# NIRGM_V3.net
KiCad netlist of a schematic drawn in EAGLE
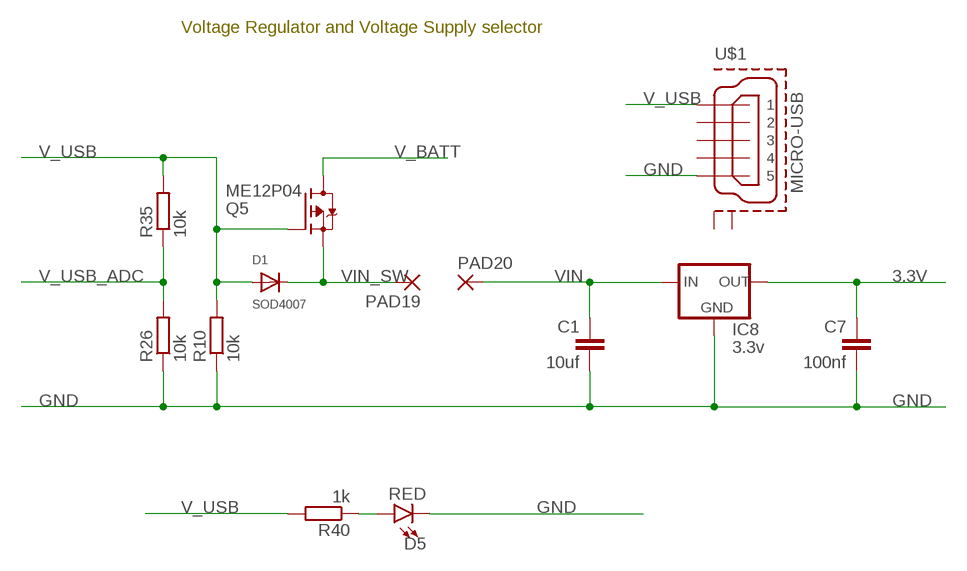
[diagram p0: schematic, sheet 1]
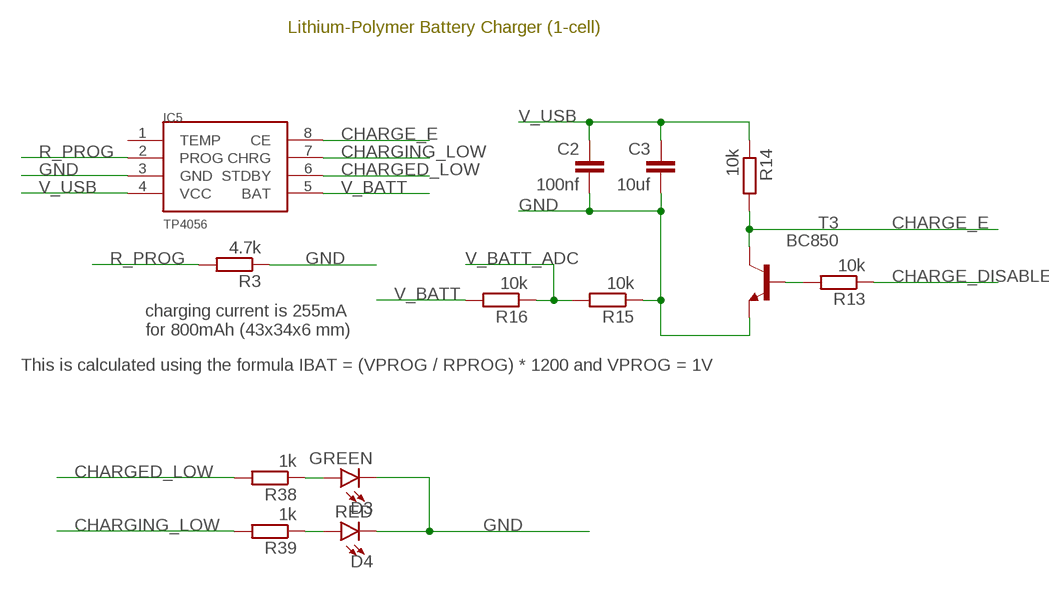
[diagram p1: schematic, sheet 2]
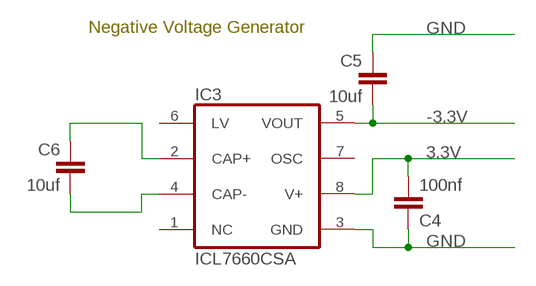
[diagram p2: schematic, sheet 3]
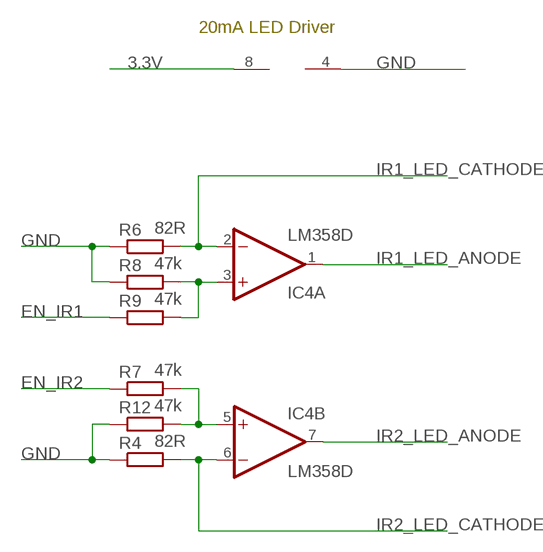
[diagram p3: schematic, sheet 4]
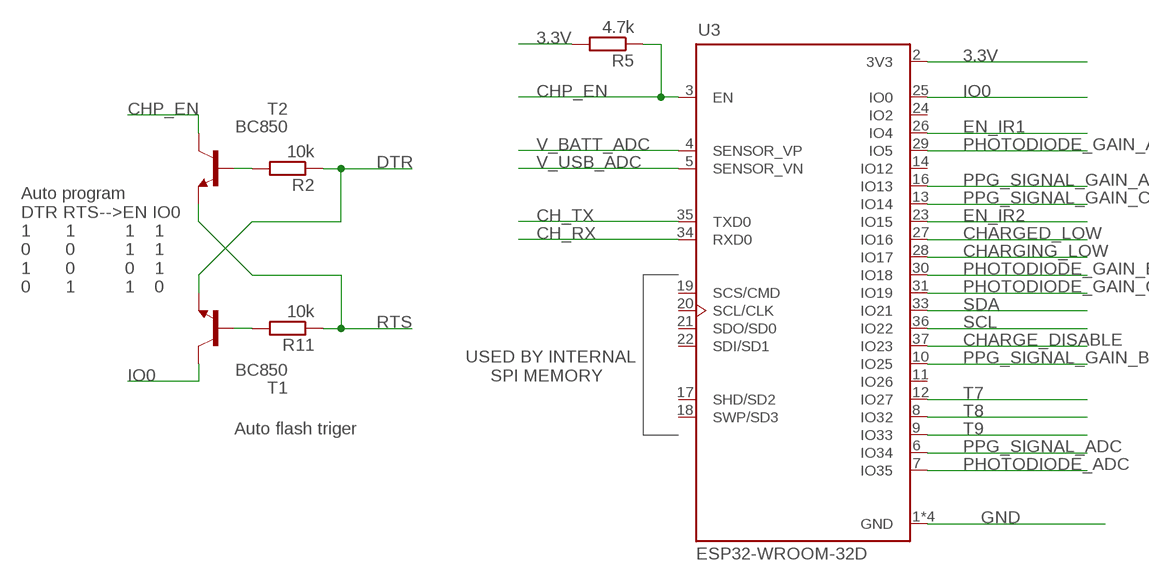
[diagram p4: schematic, sheet 5]
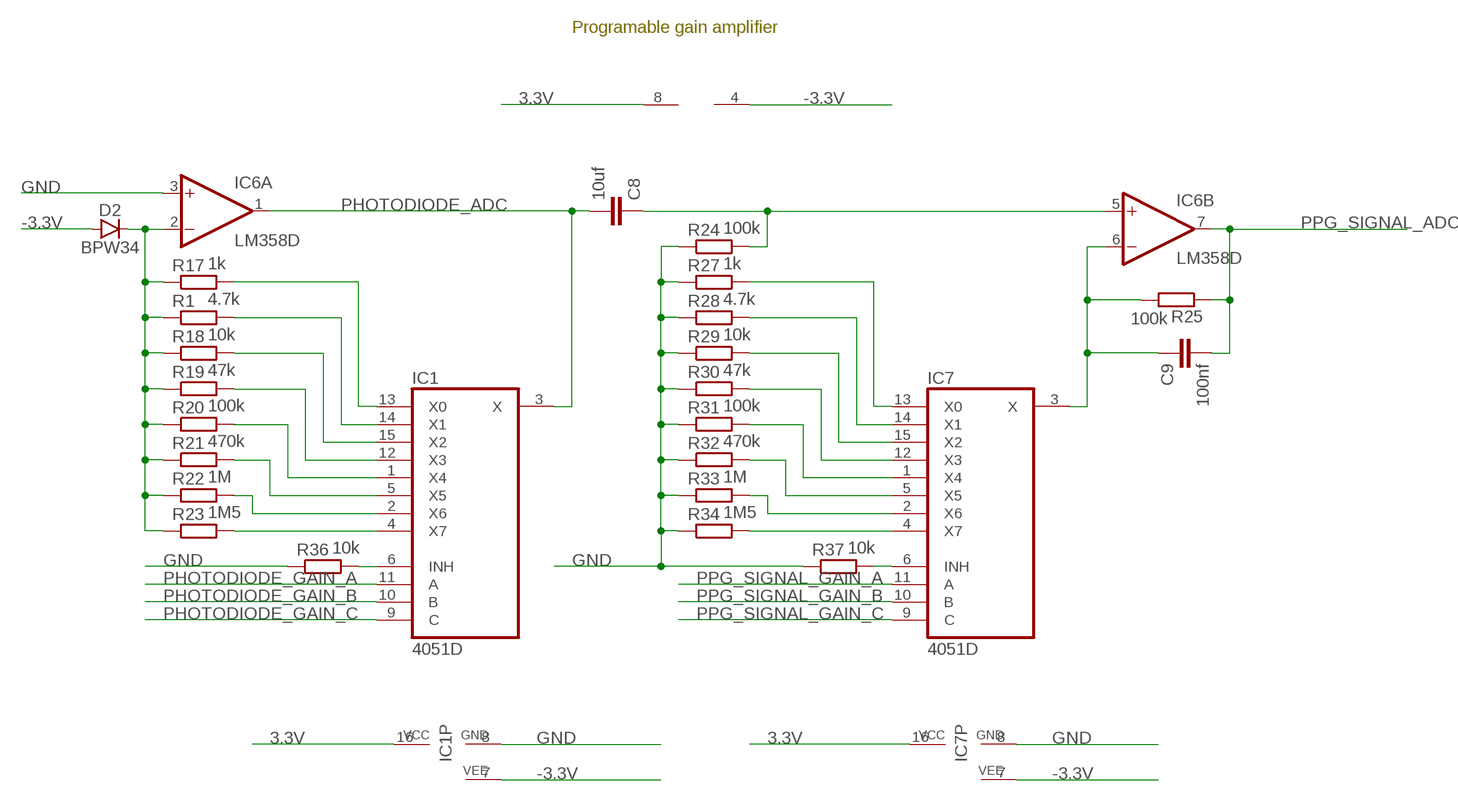
[diagram p5: schematic, sheet 6]
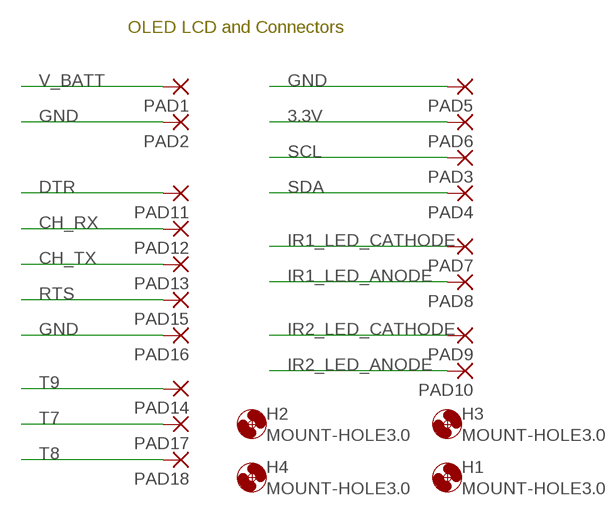
[diagram p6: schematic, sheet 7]

(export (version "E")
  (design (tool "Eeschema 10.0.6"))
  (components
    (comp (ref "C4")
      (value "100nf")
      (footprint "eagle-import:C1206K")
      (libsource (lib "eagle-import") (part "C-EUC1206K"))
    )
    (comp (ref "C5")
      (value "10uf")
      (footprint "eagle-import:C1206K")
      (libsource (lib "eagle-import") (part "C-EUC1206K"))
    )
    (comp (ref "C6")
      (value "10uf")
      (footprint "eagle-import:C1206K")
      (libsource (lib "eagle-import") (part "C-EUC1206K"))
    )
    (comp (ref "IC3")
      (value "ICL7660CSA")
      (footprint "eagle-import:SO08")
      (fields (field (name "MF") "MAXIM"))
      (libsource (lib "eagle-import") (part "ICL7660CSA"))
    )
    (comp (ref "H1")
      (value "MOUNT-HOLE3.0")
      (footprint "eagle-import:3,0")
      (libsource (lib "eagle-import") (part "MOUNT-HOLE3.0"))
    )
    (comp (ref "H2")
      (value "MOUNT-HOLE3.0")
      (footprint "eagle-import:3,0")
      (libsource (lib "eagle-import") (part "MOUNT-HOLE3.0"))
    )
    (comp (ref "H3")
      (value "MOUNT-HOLE3.0")
      (footprint "eagle-import:3,0")
      (libsource (lib "eagle-import") (part "MOUNT-HOLE3.0"))
    )
    (comp (ref "H4")
      (value "MOUNT-HOLE3.0")
      (footprint "eagle-import:3,0")
      (libsource (lib "eagle-import") (part "MOUNT-HOLE3.0"))
    )
    (comp (ref "PAD1")
      (value "WIREPADSMD5-2,5")
      (footprint "eagle-import:5-2,5")
      (libsource (lib "eagle-import") (part "WIREPADSMD5-2,5"))
    )
    (comp (ref "PAD2")
      (value "WIREPADSMD5-2,5")
      (footprint "eagle-import:5-2,5")
      (libsource (lib "eagle-import") (part "WIREPADSMD5-2,5"))
    )
    (comp (ref "PAD3")
      (value "SMD2")
      (footprint "eagle-import:SMD1,27-2,54")
      (libsource (lib "eagle-import") (part "SMD2"))
    )
    (comp (ref "PAD4")
      (value "SMD2")
      (footprint "eagle-import:SMD1,27-2,54")
      (libsource (lib "eagle-import") (part "SMD2"))
    )
    (comp (ref "PAD5")
      (value "SMD2")
      (footprint "eagle-import:SMD1,27-2,54")
      (libsource (lib "eagle-import") (part "SMD2"))
    )
    (comp (ref "PAD6")
      (value "SMD2")
      (footprint "eagle-import:SMD1,27-2,54")
      (libsource (lib "eagle-import") (part "SMD2"))
    )
    (comp (ref "PAD7")
      (value "SMD2")
      (footprint "eagle-import:SMD1,27-2,54")
      (libsource (lib "eagle-import") (part "SMD2"))
    )
    (comp (ref "PAD8")
      (value "SMD2")
      (footprint "eagle-import:SMD1,27-2,54")
      (libsource (lib "eagle-import") (part "SMD2"))
    )
    (comp (ref "PAD9")
      (value "SMD2")
      (footprint "eagle-import:SMD1,27-2,54")
      (libsource (lib "eagle-import") (part "SMD2"))
    )
    (comp (ref "PAD10")
      (value "SMD2")
      (footprint "eagle-import:SMD1,27-2,54")
      (libsource (lib "eagle-import") (part "SMD2"))
    )
    (comp (ref "PAD11")
      (value "SMD2")
      (footprint "eagle-import:SMD1,27-2,54")
      (libsource (lib "eagle-import") (part "SMD2"))
    )
    (comp (ref "PAD12")
      (value "SMD2")
      (footprint "eagle-import:SMD1,27-2,54")
      (libsource (lib "eagle-import") (part "SMD2"))
    )
    (comp (ref "PAD13")
      (value "SMD2")
      (footprint "eagle-import:SMD1,27-2,54")
      (libsource (lib "eagle-import") (part "SMD2"))
    )
    (comp (ref "PAD14")
      (value "SMD2")
      (footprint "eagle-import:SMD1,27-2,54")
      (libsource (lib "eagle-import") (part "SMD2"))
    )
    (comp (ref "PAD15")
      (value "SMD2")
      (footprint "eagle-import:SMD1,27-2,54")
      (libsource (lib "eagle-import") (part "SMD2"))
    )
    (comp (ref "PAD16")
      (value "SMD2")
      (footprint "eagle-import:SMD1,27-2,54")
      (libsource (lib "eagle-import") (part "SMD2"))
    )
    (comp (ref "PAD17")
      (value "SMD2")
      (footprint "eagle-import:SMD1,27-2,54")
      (libsource (lib "eagle-import") (part "SMD2"))
    )
    (comp (ref "PAD18")
      (value "SMD2")
      (footprint "eagle-import:SMD1,27-2,54")
      (libsource (lib "eagle-import") (part "SMD2"))
    )
    (comp (ref "C8")
      (value "10uf")
      (footprint "eagle-import:C1206K")
      (libsource (lib "eagle-import") (part "C-EUC1206K"))
    )
    (comp (ref "C9")
      (value "100nf")
      (footprint "eagle-import:C1206K")
      (libsource (lib "eagle-import") (part "C-EUC1206K"))
    )
    (comp (ref "D2")
      (value "BPW34")
      (footprint "eagle-import:BPW34")
      (libsource (lib "eagle-import") (part "BPW34"))
    )
    (comp (ref "IC1")
      (value "4051D")
      (footprint "eagle-import:SO16")
      (libsource (lib "eagle-import") (part "4051D"))
    )
    (comp (ref "IC6")
      (value "LM358D")
      (footprint "eagle-import:SO08")
      (libsource (lib "eagle-import") (part "LM358D"))
    )
    (comp (ref "IC7")
      (value "4051D")
      (footprint "eagle-import:SO16")
      (libsource (lib "eagle-import") (part "4051D"))
    )
    (comp (ref "R1")
      (value "4.7k")
      (footprint "eagle-import:R1206")
      (libsource (lib "eagle-import") (part "R-EU_R1206"))
    )
    (comp (ref "R17")
      (value "1k")
      (footprint "eagle-import:R1206")
      (libsource (lib "eagle-import") (part "R-EU_R1206"))
    )
    (comp (ref "R18")
      (value "10k")
      (footprint "eagle-import:R1206")
      (libsource (lib "eagle-import") (part "R-EU_R1206"))
    )
    (comp (ref "R19")
      (value "47k")
      (footprint "eagle-import:R1206")
      (libsource (lib "eagle-import") (part "R-EU_R1206"))
    )
    (comp (ref "R20")
      (value "100k")
      (footprint "eagle-import:R1206")
      (libsource (lib "eagle-import") (part "R-EU_R1206"))
    )
    (comp (ref "R21")
      (value "470k")
      (footprint "eagle-import:R1206")
      (libsource (lib "eagle-import") (part "R-EU_R1206"))
    )
    (comp (ref "R22")
      (value "1M")
      (footprint "eagle-import:R1206")
      (libsource (lib "eagle-import") (part "R-EU_R1206"))
    )
    (comp (ref "R23")
      (value "1M5")
      (footprint "eagle-import:R1206")
      (libsource (lib "eagle-import") (part "R-EU_R1206"))
    )
    (comp (ref "R24")
      (value "100k")
      (footprint "eagle-import:R1206")
      (libsource (lib "eagle-import") (part "R-EU_R1206"))
    )
    (comp (ref "R25")
      (value "100k")
      (footprint "eagle-import:R1206")
      (libsource (lib "eagle-import") (part "R-EU_R1206"))
    )
    (comp (ref "R27")
      (value "1k")
      (footprint "eagle-import:R1206")
      (libsource (lib "eagle-import") (part "R-EU_R1206"))
    )
    (comp (ref "R28")
      (value "4.7k")
      (footprint "eagle-import:R1206")
      (libsource (lib "eagle-import") (part "R-EU_R1206"))
    )
    (comp (ref "R29")
      (value "10k")
      (footprint "eagle-import:R1206")
      (libsource (lib "eagle-import") (part "R-EU_R1206"))
    )
    (comp (ref "R30")
      (value "47k")
      (footprint "eagle-import:R1206")
      (libsource (lib "eagle-import") (part "R-EU_R1206"))
    )
    (comp (ref "R31")
      (value "100k")
      (footprint "eagle-import:R1206")
      (libsource (lib "eagle-import") (part "R-EU_R1206"))
    )
    (comp (ref "R32")
      (value "470k")
      (footprint "eagle-import:R1206")
      (libsource (lib "eagle-import") (part "R-EU_R1206"))
    )
    (comp (ref "R33")
      (value "1M")
      (footprint "eagle-import:R1206")
      (libsource (lib "eagle-import") (part "R-EU_R1206"))
    )
    (comp (ref "R34")
      (value "1M5")
      (footprint "eagle-import:R1206")
      (libsource (lib "eagle-import") (part "R-EU_R1206"))
    )
    (comp (ref "R36")
      (value "10k")
      (footprint "eagle-import:R1206")
      (libsource (lib "eagle-import") (part "R-EU_R1206"))
    )
    (comp (ref "R37")
      (value "10k")
      (footprint "eagle-import:R1206")
      (libsource (lib "eagle-import") (part "R-EU_R1206"))
    )
    (comp (ref "IC4")
      (value "LM358D")
      (footprint "eagle-import:SO08")
      (libsource (lib "eagle-import") (part "linear_262_LM358D"))
    )
    (comp (ref "R4")
      (value "82R")
      (footprint "eagle-import:R1206")
      (libsource (lib "eagle-import") (part "R-EU_R1206"))
    )
    (comp (ref "R6")
      (value "82R")
      (footprint "eagle-import:R1206")
      (libsource (lib "eagle-import") (part "R-EU_R1206"))
    )
    (comp (ref "R7")
      (value "47k")
      (footprint "eagle-import:R1206")
      (libsource (lib "eagle-import") (part "R-EU_R1206"))
    )
    (comp (ref "R8")
      (value "47k")
      (footprint "eagle-import:R1206")
      (libsource (lib "eagle-import") (part "R-EU_R1206"))
    )
    (comp (ref "R9")
      (value "47k")
      (footprint "eagle-import:R1206")
      (libsource (lib "eagle-import") (part "R-EU_R1206"))
    )
    (comp (ref "R12")
      (value "47k")
      (footprint "eagle-import:R1206")
      (libsource (lib "eagle-import") (part "R-EU_R1206"))
    )
    (comp (ref "C2")
      (value "100nf")
      (footprint "eagle-import:C1206K")
      (libsource (lib "eagle-import") (part "C-EUC1206K"))
    )
    (comp (ref "C3")
      (value "10uf")
      (footprint "eagle-import:C1206K")
      (libsource (lib "eagle-import") (part "C-EUC1206K"))
    )
    (comp (ref "D3")
      (value "GREEN")
      (footprint "eagle-import:LED-1206")
      (libsource (lib "eagle-import") (part "LED-GREEN1206"))
    )
    (comp (ref "D4")
      (value "RED")
      (footprint "eagle-import:LED-1206")
      (libsource (lib "eagle-import") (part "LED-GREEN1206"))
    )
    (comp (ref "IC5")
      (value "TP4056")
      (footprint "eagle-import:SOP-8")
      (libsource (lib "eagle-import") (part "TP4056"))
    )
    (comp (ref "R3")
      (value "4.7k")
      (footprint "eagle-import:R1206")
      (libsource (lib "eagle-import") (part "R-EU_R1206"))
    )
    (comp (ref "R13")
      (value "10k")
      (footprint "eagle-import:R1206")
      (libsource (lib "eagle-import") (part "R-EU_R1206"))
    )
    (comp (ref "R14")
      (value "10k")
      (footprint "eagle-import:R1206")
      (libsource (lib "eagle-import") (part "R-EU_R1206"))
    )
    (comp (ref "R15")
      (value "10k")
      (footprint "eagle-import:R1206")
      (libsource (lib "eagle-import") (part "R-EU_R1206"))
    )
    (comp (ref "R16")
      (value "10k")
      (footprint "eagle-import:R1206")
      (libsource (lib "eagle-import") (part "R-EU_R1206"))
    )
    (comp (ref "R38")
      (value "1k")
      (footprint "eagle-import:R1206")
      (libsource (lib "eagle-import") (part "R-EU_R1206"))
    )
    (comp (ref "R39")
      (value "1k")
      (footprint "eagle-import:R1206")
      (libsource (lib "eagle-import") (part "R-EU_R1206"))
    )
    (comp (ref "T3")
      (value "BC850")
      (footprint "eagle-import:SOT23")
      (libsource (lib "eagle-import") (part "BC850"))
    )
    (comp (ref "R2")
      (value "10k")
      (footprint "eagle-import:R1206")
      (libsource (lib "eagle-import") (part "R-EU_R1206"))
    )
    (comp (ref "R5")
      (value "4.7k")
      (footprint "eagle-import:R1206")
      (libsource (lib "eagle-import") (part "R-EU_R1206"))
    )
    (comp (ref "R11")
      (value "10k")
      (footprint "eagle-import:R1206")
      (libsource (lib "eagle-import") (part "R-EU_R1206"))
    )
    (comp (ref "T1")
      (value "BC850")
      (footprint "eagle-import:SOT23")
      (libsource (lib "eagle-import") (part "BC850"))
    )
    (comp (ref "T2")
      (value "BC850")
      (footprint "eagle-import:SOT23")
      (libsource (lib "eagle-import") (part "BC850"))
    )
    (comp (ref "U3")
      (value "ESP32-WROOM-32D")
      (footprint "eagle-import:MODULE_ESP32-WROOM-32D")
      (fields (field (name "MF") "Espressif Systems"))
      (libsource (lib "eagle-import") (part "ESP32-WROOM-32D"))
    )
    (comp (ref "C1")
      (value "10uf")
      (footprint "eagle-import:C1206K")
      (libsource (lib "eagle-import") (part "C-EUC1206K"))
    )
    (comp (ref "C7")
      (value "100nf")
      (footprint "eagle-import:C1206K")
      (libsource (lib "eagle-import") (part "C-EUC1206K"))
    )
    (comp (ref "D1")
      (value "SOD4007")
      (footprint "eagle-import:SOD-123FL")
      (libsource (lib "eagle-import") (part "DIODE_SOD-123FL"))
    )
    (comp (ref "D5")
      (value "RED")
      (footprint "eagle-import:LED-1206")
      (libsource (lib "eagle-import") (part "LED-GREEN1206"))
    )
    (comp (ref "IC8")
      (value "3.3v")
      (footprint "eagle-import:TO252")
      (libsource (lib "eagle-import") (part "LM1117TO252"))
    )
    (comp (ref "PAD19")
      (value "SMD2")
      (footprint "eagle-import:SMD1,27-2,54")
      (libsource (lib "eagle-import") (part "SMD2"))
    )
    (comp (ref "PAD20")
      (value "SMD2")
      (footprint "eagle-import:SMD1,27-2,54")
      (libsource (lib "eagle-import") (part "SMD2"))
    )
    (comp (ref "Q5")
      (value "ME12P04")
      (footprint "eagle-import:TO252")
      (libsource (lib "eagle-import") (part "FDD4141TO252"))
    )
    (comp (ref "R10")
      (value "10k")
      (footprint "eagle-import:R1206")
      (libsource (lib "eagle-import") (part "R-EU_R1206"))
    )
    (comp (ref "R26")
      (value "10k")
      (footprint "eagle-import:R1206")
      (libsource (lib "eagle-import") (part "R-EU_R1206"))
    )
    (comp (ref "R35")
      (value "10k")
      (footprint "eagle-import:R1206")
      (libsource (lib "eagle-import") (part "R-EU_R1206"))
    )
    (comp (ref "R40")
      (value "1k")
      (footprint "eagle-import:R1206")
      (libsource (lib "eagle-import") (part "R-EU_R1206"))
    )
    (comp (ref "U$1")
      (value "MICRO-USB")
      (footprint "eagle-import:47589-0001")
      (libsource (lib "eagle-import") (part "MICRO-USB-RECEPTACLE47589-0001"))
    )
  )
  (nets
    (net (code "1") (name "-3.3V") (class "Default")
      (node (ref "C5") (pin "2") (pinfunction "2_2") (pintype "passive"))
      (node (ref "D2") (pin "P$1") (pinfunction "A_P$1") (pintype "passive"))
      (node (ref "IC1") (pin "7") (pinfunction "VEE_7") (pintype "power_in"))
      (node (ref "IC3") (pin "5") (pinfunction "VOUT_5") (pintype "output"))
      (node (ref "IC6") (pin "4") (pinfunction "V-_4") (pintype "power_in"))
      (node (ref "IC7") (pin "7") (pinfunction "VEE_7") (pintype "power_in"))
    )
    (net (code "2") (name "3.3V") (class "Default")
      (node (ref "C4") (pin "2") (pinfunction "2_2") (pintype "passive"))
      (node (ref "C7") (pin "1") (pinfunction "1_1") (pintype "passive"))
      (node (ref "IC1") (pin "16") (pinfunction "VCC_16") (pintype "power_in"))
      (node (ref "IC3") (pin "8") (pinfunction "V+_8") (pintype "power_in"))
      (node (ref "IC4") (pin "8") (pinfunction "V+_8") (pintype "power_in"))
      (node (ref "IC6") (pin "8") (pinfunction "V+_8") (pintype "power_in"))
      (node (ref "IC7") (pin "16") (pinfunction "VCC_16") (pintype "power_in"))
      (node (ref "IC8") (pin "3") (pinfunction "OUT_3") (pintype "passive"))
      (node (ref "PAD6") (pin "1") (pinfunction "P_1") (pintype "passive"))
      (node (ref "R5") (pin "2") (pinfunction "2_2") (pintype "passive"))
      (node (ref "U3") (pin "2") (pinfunction "3V3_2") (pintype "power_in"))
    )
    (net (code "3") (name "CHARGED_LOW") (class "Default")
      (node (ref "IC5") (pin "6") (pinfunction "STDBY_6") (pintype "bidirectional"))
      (node (ref "R38") (pin "2") (pinfunction "2_2") (pintype "passive"))
      (node (ref "U3") (pin "27") (pinfunction "IO16_27") (pintype "bidirectional"))
    )
    (net (code "4") (name "CHARGE_DISABLE") (class "Default")
      (node (ref "R13") (pin "1") (pinfunction "1_1") (pintype "passive"))
      (node (ref "U3") (pin "37") (pinfunction "IO23_37") (pintype "bidirectional"))
    )
    (net (code "5") (name "CHARGE_E") (class "Default")
      (node (ref "IC5") (pin "8") (pinfunction "CE_8") (pintype "bidirectional"))
      (node (ref "R14") (pin "2") (pinfunction "2_2") (pintype "passive"))
      (node (ref "T3") (pin "3") (pinfunction "C_3") (pintype "passive"))
    )
    (net (code "6") (name "CHARGING_LOW") (class "Default")
      (node (ref "IC5") (pin "7") (pinfunction "CHRG_7") (pintype "bidirectional"))
      (node (ref "R39") (pin "2") (pinfunction "2_2") (pintype "passive"))
      (node (ref "U3") (pin "28") (pinfunction "IO17_28") (pintype "bidirectional"))
    )
    (net (code "7") (name "CHP_EN") (class "Default")
      (node (ref "R5") (pin "1") (pinfunction "1_1") (pintype "passive"))
      (node (ref "T2") (pin "3") (pinfunction "C_3") (pintype "passive"))
      (node (ref "U3") (pin "3") (pinfunction "EN_3") (pintype "input"))
    )
    (net (code "8") (name "CH_RX") (class "Default")
      (node (ref "PAD12") (pin "1") (pinfunction "P_1") (pintype "passive"))
      (node (ref "U3") (pin "34") (pinfunction "RXD0_34") (pintype "bidirectional"))
    )
    (net (code "9") (name "CH_TX") (class "Default")
      (node (ref "PAD13") (pin "1") (pinfunction "P_1") (pintype "passive"))
      (node (ref "U3") (pin "35") (pinfunction "TXD0_35") (pintype "bidirectional"))
    )
    (net (code "10") (name "DTR") (class "Default")
      (node (ref "PAD11") (pin "1") (pinfunction "P_1") (pintype "passive"))
      (node (ref "R2") (pin "1") (pinfunction "1_1") (pintype "passive"))
      (node (ref "T1") (pin "2") (pinfunction "E_2") (pintype "passive"))
    )
    (net (code "11") (name "EN_IR1") (class "Default")
      (node (ref "R9") (pin "1") (pinfunction "1_1") (pintype "passive"))
      (node (ref "U3") (pin "26") (pinfunction "IO4_26") (pintype "bidirectional"))
    )
    (net (code "12") (name "EN_IR2") (class "Default")
      (node (ref "R7") (pin "1") (pinfunction "1_1") (pintype "passive"))
      (node (ref "U3") (pin "23") (pinfunction "IO15_23") (pintype "bidirectional"))
    )
    (net (code "13") (name "GND") (class "Default")
      (node (ref "C1") (pin "2") (pinfunction "2_2") (pintype "passive"))
      (node (ref "C2") (pin "2") (pinfunction "2_2") (pintype "passive"))
      (node (ref "C3") (pin "2") (pinfunction "2_2") (pintype "passive"))
      (node (ref "C4") (pin "1") (pinfunction "1_1") (pintype "passive"))
      (node (ref "C5") (pin "1") (pinfunction "1_1") (pintype "passive"))
      (node (ref "C7") (pin "2") (pinfunction "2_2") (pintype "passive"))
      (node (ref "D3") (pin "C") (pinfunction "C_C") (pintype "passive"))
      (node (ref "D4") (pin "C") (pinfunction "C_C") (pintype "passive"))
      (node (ref "D5") (pin "C") (pinfunction "C_C") (pintype "passive"))
      (node (ref "IC1") (pin "8") (pinfunction "GND_8") (pintype "power_in"))
      (node (ref "IC3") (pin "3") (pinfunction "GND_3") (pintype "power_in"))
      (node (ref "IC4") (pin "4") (pinfunction "V-_4") (pintype "power_in"))
      (node (ref "IC5") (pin "3") (pinfunction "GND_3") (pintype "bidirectional"))
      (node (ref "IC6") (pin "3") (pinfunction "+IN_3") (pintype "input"))
      (node (ref "IC7") (pin "8") (pinfunction "GND_8") (pintype "power_in"))
      (node (ref "IC8") (pin "1") (pinfunction "GND_1") (pintype "input"))
      (node (ref "PAD16") (pin "1") (pinfunction "P_1") (pintype "passive"))
      (node (ref "PAD2") (pin "1") (pinfunction "P_1") (pintype "passive"))
      (node (ref "PAD5") (pin "1") (pinfunction "P_1") (pintype "passive"))
      (node (ref "R10") (pin "1") (pinfunction "1_1") (pintype "passive"))
      (node (ref "R12") (pin "1") (pinfunction "1_1") (pintype "passive"))
      (node (ref "R15") (pin "1") (pinfunction "1_1") (pintype "passive"))
      (node (ref "R24") (pin "1") (pinfunction "1_1") (pintype "passive"))
      (node (ref "R26") (pin "1") (pinfunction "1_1") (pintype "passive"))
      (node (ref "R27") (pin "1") (pinfunction "1_1") (pintype "passive"))
      (node (ref "R28") (pin "1") (pinfunction "1_1") (pintype "passive"))
      (node (ref "R29") (pin "1") (pinfunction "1_1") (pintype "passive"))
      (node (ref "R3") (pin "1") (pinfunction "1_1") (pintype "passive"))
      (node (ref "R30") (pin "1") (pinfunction "1_1") (pintype "passive"))
      (node (ref "R31") (pin "1") (pinfunction "1_1") (pintype "passive"))
      (node (ref "R32") (pin "1") (pinfunction "1_1") (pintype "passive"))
      (node (ref "R33") (pin "1") (pinfunction "1_1") (pintype "passive"))
      (node (ref "R34") (pin "1") (pinfunction "1_1") (pintype "passive"))
      (node (ref "R36") (pin "1") (pinfunction "1_1") (pintype "passive"))
      (node (ref "R37") (pin "1") (pinfunction "1_1") (pintype "passive"))
      (node (ref "R4") (pin "1") (pinfunction "1_1") (pintype "passive"))
      (node (ref "R6") (pin "1") (pinfunction "1_1") (pintype "passive"))
      (node (ref "R8") (pin "1") (pinfunction "1_1") (pintype "passive"))
      (node (ref "T3") (pin "2") (pinfunction "E_2") (pintype "passive"))
      (node (ref "U$1") (pin "5") (pinfunction "5_5") (pintype "input"))
      (node (ref "U3") (pin "1") (pinfunction "GND_1") (pintype "power_in"))
      (node (ref "U3") (pin "15") (pinfunction "GND_15") (pintype "power_in"))
      (node (ref "U3") (pin "38") (pinfunction "GND_38") (pintype "power_in"))
      (node (ref "U3") (pin "39") (pinfunction "GND_39") (pintype "power_in"))
    )
    (net (code "14") (name "IO0") (class "Default")
      (node (ref "T1") (pin "3") (pinfunction "C_3") (pintype "passive"))
      (node (ref "U3") (pin "25") (pinfunction "IO0_25") (pintype "bidirectional"))
    )
    (net (code "15") (name "IR1_LED_ANODE") (class "Default")
      (node (ref "IC4") (pin "1") (pinfunction "OUT_1") (pintype "output"))
      (node (ref "PAD8") (pin "1") (pinfunction "P_1") (pintype "passive"))
    )
    (net (code "16") (name "IR1_LED_CATHODE") (class "Default")
      (node (ref "IC4") (pin "2") (pinfunction "-IN_2") (pintype "input"))
      (node (ref "PAD7") (pin "1") (pinfunction "P_1") (pintype "passive"))
      (node (ref "R6") (pin "2") (pinfunction "2_2") (pintype "passive"))
    )
    (net (code "17") (name "IR2_LED_ANODE") (class "Default")
      (node (ref "IC4") (pin "7") (pinfunction "OUT_7") (pintype "output"))
      (node (ref "PAD10") (pin "1") (pinfunction "P_1") (pintype "passive"))
    )
    (net (code "18") (name "IR2_LED_CATHODE") (class "Default")
      (node (ref "IC4") (pin "6") (pinfunction "-IN_6") (pintype "input"))
      (node (ref "PAD9") (pin "1") (pinfunction "P_1") (pintype "passive"))
      (node (ref "R4") (pin "2") (pinfunction "2_2") (pintype "passive"))
    )
    (net (code "19") (name "Net-(D2-C)") (class "Default")
      (node (ref "D2") (pin "P$2") (pinfunction "C_P$2") (pintype "passive"))
      (node (ref "IC6") (pin "2") (pinfunction "-IN_2") (pintype "input"))
      (node (ref "R1") (pin "1") (pinfunction "1_1") (pintype "passive"))
      (node (ref "R17") (pin "1") (pinfunction "1_1") (pintype "passive"))
      (node (ref "R18") (pin "1") (pinfunction "1_1") (pintype "passive"))
      (node (ref "R19") (pin "1") (pinfunction "1_1") (pintype "passive"))
      (node (ref "R20") (pin "1") (pinfunction "1_1") (pintype "passive"))
      (node (ref "R21") (pin "1") (pinfunction "1_1") (pintype "passive"))
      (node (ref "R22") (pin "1") (pinfunction "1_1") (pintype "passive"))
      (node (ref "R23") (pin "1") (pinfunction "1_1") (pintype "passive"))
    )
    (net (code "20") (name "Net-(D3-PadA)") (class "Default")
      (node (ref "D3") (pin "A") (pinfunction "A_A") (pintype "passive"))
      (node (ref "R38") (pin "1") (pinfunction "1_1") (pintype "passive"))
    )
    (net (code "21") (name "Net-(D4-PadA)") (class "Default")
      (node (ref "D4") (pin "A") (pinfunction "A_A") (pintype "passive"))
      (node (ref "R39") (pin "1") (pinfunction "1_1") (pintype "passive"))
    )
    (net (code "22") (name "Net-(D5-PadA)") (class "Default")
      (node (ref "D5") (pin "A") (pinfunction "A_A") (pintype "passive"))
      (node (ref "R40") (pin "1") (pinfunction "1_1") (pintype "passive"))
    )
    (net (code "23") (name "Net-(IC1A-INH)") (class "Default")
      (node (ref "IC1") (pin "6") (pinfunction "INH_6") (pintype "input"))
      (node (ref "R36") (pin "2") (pinfunction "2_2") (pintype "passive"))
    )
    (net (code "24") (name "Net-(IC1A-X0)") (class "Default")
      (node (ref "IC1") (pin "13") (pinfunction "X0_13") (pintype "bidirectional"))
      (node (ref "R17") (pin "2") (pinfunction "2_2") (pintype "passive"))
    )
    (net (code "25") (name "Net-(IC1A-X1)") (class "Default")
      (node (ref "IC1") (pin "14") (pinfunction "X1_14") (pintype "bidirectional"))
      (node (ref "R1") (pin "2") (pinfunction "2_2") (pintype "passive"))
    )
    (net (code "26") (name "Net-(IC1A-X2)") (class "Default")
      (node (ref "IC1") (pin "15") (pinfunction "X2_15") (pintype "bidirectional"))
      (node (ref "R18") (pin "2") (pinfunction "2_2") (pintype "passive"))
    )
    (net (code "27") (name "Net-(IC1A-X3)") (class "Default")
      (node (ref "IC1") (pin "12") (pinfunction "X3_12") (pintype "bidirectional"))
      (node (ref "R19") (pin "2") (pinfunction "2_2") (pintype "passive"))
    )
    (net (code "28") (name "Net-(IC1A-X4)") (class "Default")
      (node (ref "IC1") (pin "1") (pinfunction "X4_1") (pintype "bidirectional"))
      (node (ref "R20") (pin "2") (pinfunction "2_2") (pintype "passive"))
    )
    (net (code "29") (name "Net-(IC1A-X5)") (class "Default")
      (node (ref "IC1") (pin "5") (pinfunction "X5_5") (pintype "bidirectional"))
      (node (ref "R21") (pin "2") (pinfunction "2_2") (pintype "passive"))
    )
    (net (code "30") (name "Net-(IC1A-X6)") (class "Default")
      (node (ref "IC1") (pin "2") (pinfunction "X6_2") (pintype "bidirectional"))
      (node (ref "R22") (pin "2") (pinfunction "2_2") (pintype "passive"))
    )
    (net (code "31") (name "Net-(IC1A-X7)") (class "Default")
      (node (ref "IC1") (pin "4") (pinfunction "X7_4") (pintype "bidirectional"))
      (node (ref "R23") (pin "2") (pinfunction "2_2") (pintype "passive"))
    )
    (net (code "32") (name "Net-(IC3-CAP+)") (class "Default")
      (node (ref "C6") (pin "1") (pinfunction "1_1") (pintype "passive"))
      (node (ref "IC3") (pin "2") (pinfunction "CAP+_2") (pintype "passive"))
    )
    (net (code "33") (name "Net-(IC3-CAP-)") (class "Default")
      (node (ref "C6") (pin "2") (pinfunction "2_2") (pintype "passive"))
      (node (ref "IC3") (pin "4") (pinfunction "CAP-_4") (pintype "passive"))
    )
    (net (code "34") (name "Net-(IC4A-+IN)") (class "Default")
      (node (ref "IC4") (pin "3") (pinfunction "+IN_3") (pintype "input"))
      (node (ref "R8") (pin "2") (pinfunction "2_2") (pintype "passive"))
      (node (ref "R9") (pin "2") (pinfunction "2_2") (pintype "passive"))
    )
    (net (code "35") (name "Net-(IC4B-+IN)") (class "Default")
      (node (ref "IC4") (pin "5") (pinfunction "+IN_5") (pintype "input"))
      (node (ref "R12") (pin "2") (pinfunction "2_2") (pintype "passive"))
      (node (ref "R7") (pin "2") (pinfunction "2_2") (pintype "passive"))
    )
    (net (code "36") (name "Net-(IC6B-+IN)") (class "Default")
      (node (ref "C8") (pin "1") (pinfunction "1_1") (pintype "passive"))
      (node (ref "IC6") (pin "5") (pinfunction "+IN_5") (pintype "input"))
      (node (ref "R24") (pin "2") (pinfunction "2_2") (pintype "passive"))
    )
    (net (code "37") (name "Net-(IC6B--IN)") (class "Default")
      (node (ref "C9") (pin "1") (pinfunction "1_1") (pintype "passive"))
      (node (ref "IC6") (pin "6") (pinfunction "-IN_6") (pintype "input"))
      (node (ref "IC7") (pin "3") (pinfunction "X_3") (pintype "bidirectional"))
      (node (ref "R25") (pin "2") (pinfunction "2_2") (pintype "passive"))
    )
    (net (code "38") (name "Net-(IC7A-INH)") (class "Default")
      (node (ref "IC7") (pin "6") (pinfunction "INH_6") (pintype "input"))
      (node (ref "R37") (pin "2") (pinfunction "2_2") (pintype "passive"))
    )
    (net (code "39") (name "Net-(IC7A-X0)") (class "Default")
      (node (ref "IC7") (pin "13") (pinfunction "X0_13") (pintype "bidirectional"))
      (node (ref "R27") (pin "2") (pinfunction "2_2") (pintype "passive"))
    )
    (net (code "40") (name "Net-(IC7A-X1)") (class "Default")
      (node (ref "IC7") (pin "14") (pinfunction "X1_14") (pintype "bidirectional"))
      (node (ref "R28") (pin "2") (pinfunction "2_2") (pintype "passive"))
    )
    (net (code "41") (name "Net-(IC7A-X2)") (class "Default")
      (node (ref "IC7") (pin "15") (pinfunction "X2_15") (pintype "bidirectional"))
      (node (ref "R29") (pin "2") (pinfunction "2_2") (pintype "passive"))
    )
    (net (code "42") (name "Net-(IC7A-X3)") (class "Default")
      (node (ref "IC7") (pin "12") (pinfunction "X3_12") (pintype "bidirectional"))
      (node (ref "R30") (pin "2") (pinfunction "2_2") (pintype "passive"))
    )
    (net (code "43") (name "Net-(IC7A-X4)") (class "Default")
      (node (ref "IC7") (pin "1") (pinfunction "X4_1") (pintype "bidirectional"))
      (node (ref "R31") (pin "2") (pinfunction "2_2") (pintype "passive"))
    )
    (net (code "44") (name "Net-(IC7A-X5)") (class "Default")
      (node (ref "IC7") (pin "5") (pinfunction "X5_5") (pintype "bidirectional"))
      (node (ref "R32") (pin "2") (pinfunction "2_2") (pintype "passive"))
    )
    (net (code "45") (name "Net-(IC7A-X6)") (class "Default")
      (node (ref "IC7") (pin "2") (pinfunction "X6_2") (pintype "bidirectional"))
      (node (ref "R33") (pin "2") (pinfunction "2_2") (pintype "passive"))
    )
    (net (code "46") (name "Net-(IC7A-X7)") (class "Default")
      (node (ref "IC7") (pin "4") (pinfunction "X7_4") (pintype "bidirectional"))
      (node (ref "R34") (pin "2") (pinfunction "2_2") (pintype "passive"))
    )
    (net (code "47") (name "Net-(T1-B)") (class "Default")
      (node (ref "R11") (pin "2") (pinfunction "2_2") (pintype "passive"))
      (node (ref "T1") (pin "1") (pinfunction "B_1") (pintype "passive"))
    )
    (net (code "48") (name "Net-(T2-B)") (class "Default")
      (node (ref "R2") (pin "2") (pinfunction "2_2") (pintype "passive"))
      (node (ref "T2") (pin "1") (pinfunction "B_1") (pintype "passive"))
    )
    (net (code "49") (name "Net-(T3-B)") (class "Default")
      (node (ref "R13") (pin "2") (pinfunction "2_2") (pintype "passive"))
      (node (ref "T3") (pin "1") (pinfunction "B_1") (pintype "passive"))
    )
    (net (code "50") (name "PHOTODIODE_ADC") (class "Default")
      (node (ref "C8") (pin "2") (pinfunction "2_2") (pintype "passive"))
      (node (ref "IC1") (pin "3") (pinfunction "X_3") (pintype "bidirectional"))
      (node (ref "IC6") (pin "1") (pinfunction "OUT_1") (pintype "output"))
      (node (ref "U3") (pin "7") (pinfunction "IO35_7") (pintype "bidirectional"))
    )
    (net (code "51") (name "PHOTODIODE_GAIN_A") (class "Default")
      (node (ref "IC1") (pin "11") (pinfunction "A_11") (pintype "input"))
      (node (ref "U3") (pin "29") (pinfunction "IO5_29") (pintype "bidirectional"))
    )
    (net (code "52") (name "PHOTODIODE_GAIN_B") (class "Default")
      (node (ref "IC1") (pin "10") (pinfunction "B_10") (pintype "input"))
      (node (ref "U3") (pin "30") (pinfunction "IO18_30") (pintype "bidirectional"))
    )
    (net (code "53") (name "PHOTODIODE_GAIN_C") (class "Default")
      (node (ref "IC1") (pin "9") (pinfunction "C_9") (pintype "input"))
      (node (ref "U3") (pin "31") (pinfunction "IO19_31") (pintype "bidirectional"))
    )
    (net (code "54") (name "PPG_SIGNAL_ADC") (class "Default")
      (node (ref "C9") (pin "2") (pinfunction "2_2") (pintype "passive"))
      (node (ref "IC6") (pin "7") (pinfunction "OUT_7") (pintype "output"))
      (node (ref "R25") (pin "1") (pinfunction "1_1") (pintype "passive"))
      (node (ref "U3") (pin "6") (pinfunction "IO34_6") (pintype "bidirectional"))
    )
    (net (code "55") (name "PPG_SIGNAL_GAIN_A") (class "Default")
      (node (ref "IC7") (pin "11") (pinfunction "A_11") (pintype "input"))
      (node (ref "U3") (pin "16") (pinfunction "IO13_16") (pintype "bidirectional"))
    )
    (net (code "56") (name "PPG_SIGNAL_GAIN_B") (class "Default")
      (node (ref "IC7") (pin "10") (pinfunction "B_10") (pintype "input"))
      (node (ref "U3") (pin "10") (pinfunction "IO25_10") (pintype "bidirectional"))
    )
    (net (code "57") (name "PPG_SIGNAL_GAIN_C") (class "Default")
      (node (ref "IC7") (pin "9") (pinfunction "C_9") (pintype "input"))
      (node (ref "U3") (pin "13") (pinfunction "IO14_13") (pintype "bidirectional"))
    )
    (net (code "58") (name "RTS") (class "Default")
      (node (ref "PAD15") (pin "1") (pinfunction "P_1") (pintype "passive"))
      (node (ref "R11") (pin "1") (pinfunction "1_1") (pintype "passive"))
      (node (ref "T2") (pin "2") (pinfunction "E_2") (pintype "passive"))
    )
    (net (code "59") (name "R_PROG") (class "Default")
      (node (ref "IC5") (pin "2") (pinfunction "PROG_2") (pintype "bidirectional"))
      (node (ref "R3") (pin "2") (pinfunction "2_2") (pintype "passive"))
    )
    (net (code "60") (name "SCL") (class "Default")
      (node (ref "PAD3") (pin "1") (pinfunction "P_1") (pintype "passive"))
      (node (ref "U3") (pin "36") (pinfunction "IO22_36") (pintype "bidirectional"))
    )
    (net (code "61") (name "SDA") (class "Default")
      (node (ref "PAD4") (pin "1") (pinfunction "P_1") (pintype "passive"))
      (node (ref "U3") (pin "33") (pinfunction "IO21_33") (pintype "bidirectional"))
    )
    (net (code "62") (name "T7") (class "Default")
      (node (ref "PAD17") (pin "1") (pinfunction "P_1") (pintype "passive"))
      (node (ref "U3") (pin "12") (pinfunction "IO27_12") (pintype "bidirectional"))
    )
    (net (code "63") (name "T8") (class "Default")
      (node (ref "PAD18") (pin "1") (pinfunction "P_1") (pintype "passive"))
      (node (ref "U3") (pin "8") (pinfunction "IO32_8") (pintype "bidirectional"))
    )
    (net (code "64") (name "T9") (class "Default")
      (node (ref "PAD14") (pin "1") (pinfunction "P_1") (pintype "passive"))
      (node (ref "U3") (pin "9") (pinfunction "IO33_9") (pintype "bidirectional"))
    )
    (net (code "65") (name "VIN") (class "Default")
      (node (ref "C1") (pin "1") (pinfunction "1_1") (pintype "passive"))
      (node (ref "IC8") (pin "2") (pinfunction "IN_2") (pintype "input"))
      (node (ref "PAD20") (pin "1") (pinfunction "P_1") (pintype "passive"))
    )
    (net (code "66") (name "VIN_SW") (class "Default")
      (node (ref "D1") (pin "C") (pinfunction "C_C") (pintype "passive"))
      (node (ref "PAD19") (pin "1") (pinfunction "P_1") (pintype "passive"))
      (node (ref "Q5") (pin "2") (pinfunction "S_2") (pintype "passive"))
    )
    (net (code "67") (name "V_BATT") (class "Default")
      (node (ref "IC5") (pin "5") (pinfunction "BAT_5") (pintype "bidirectional"))
      (node (ref "PAD1") (pin "1") (pinfunction "P_1") (pintype "passive"))
      (node (ref "Q5") (pin "3") (pinfunction "D_3") (pintype "passive"))
      (node (ref "R16") (pin "2") (pinfunction "2_2") (pintype "passive"))
    )
    (net (code "68") (name "V_BATT_ADC") (class "Default")
      (node (ref "R15") (pin "2") (pinfunction "2_2") (pintype "passive"))
      (node (ref "R16") (pin "1") (pinfunction "1_1") (pintype "passive"))
      (node (ref "U3") (pin "4") (pinfunction "SENSOR_VP_4") (pintype "input"))
    )
    (net (code "69") (name "V_USB") (class "Default")
      (node (ref "C2") (pin "1") (pinfunction "1_1") (pintype "passive"))
      (node (ref "C3") (pin "1") (pinfunction "1_1") (pintype "passive"))
      (node (ref "D1") (pin "A") (pinfunction "A_A") (pintype "passive"))
      (node (ref "IC5") (pin "4") (pinfunction "VCC_4") (pintype "bidirectional"))
      (node (ref "Q5") (pin "1") (pinfunction "G_1") (pintype "passive"))
      (node (ref "R10") (pin "2") (pinfunction "2_2") (pintype "passive"))
      (node (ref "R14") (pin "1") (pinfunction "1_1") (pintype "passive"))
      (node (ref "R35") (pin "2") (pinfunction "2_2") (pintype "passive"))
      (node (ref "R40") (pin "2") (pinfunction "2_2") (pintype "passive"))
      (node (ref "U$1") (pin "1") (pinfunction "1_1") (pintype "input"))
    )
    (net (code "70") (name "V_USB_ADC") (class "Default")
      (node (ref "R26") (pin "2") (pinfunction "2_2") (pintype "passive"))
      (node (ref "R35") (pin "1") (pinfunction "1_1") (pintype "passive"))
      (node (ref "U3") (pin "5") (pinfunction "SENSOR_VN_5") (pintype "input"))
    )
    (net (code "71") (name "unconnected-(IC3-LV-Pad6)") (class "Default")
      (node (ref "IC3") (pin "6") (pinfunction "LV_6") (pintype "passive"))
    )
    (net (code "72") (name "unconnected-(IC3-NC-Pad1)") (class "Default")
      (node (ref "IC3") (pin "1") (pinfunction "NC_1") (pintype "no_connect"))
    )
    (net (code "73") (name "unconnected-(IC3-OSC-Pad7)") (class "Default")
      (node (ref "IC3") (pin "7") (pinfunction "OSC_7") (pintype "output"))
    )
    (net (code "74") (name "unconnected-(IC5-TEMP-Pad1)") (class "Default")
      (node (ref "IC5") (pin "1") (pinfunction "TEMP_1") (pintype "bidirectional"))
    )
    (net (code "75") (name "unconnected-(U$1-GND1-PadP$1)") (class "Default")
      (node (ref "U$1") (pin "P$1") (pinfunction "GND1_P$1") (pintype "bidirectional"))
    )
    (net (code "76") (name "unconnected-(U$1-GND2-PadP$2)") (class "Default")
      (node (ref "U$1") (pin "P$2") (pinfunction "GND2_P$2") (pintype "bidirectional"))
    )
    (net (code "77") (name "unconnected-(U$1-Pad2)") (class "Default")
      (node (ref "U$1") (pin "2") (pinfunction "2_2") (pintype "input"))
    )
    (net (code "78") (name "unconnected-(U$1-Pad3)") (class "Default")
      (node (ref "U$1") (pin "3") (pinfunction "3_3") (pintype "input"))
    )
    (net (code "79") (name "unconnected-(U$1-Pad4)") (class "Default")
      (node (ref "U$1") (pin "4") (pinfunction "4_4") (pintype "input"))
    )
    (net (code "80") (name "unconnected-(U3-IO2-Pad24)") (class "Default")
      (node (ref "U3") (pin "24") (pinfunction "IO2_24") (pintype "bidirectional"))
    )
    (net (code "81") (name "unconnected-(U3-IO12-Pad14)") (class "Default")
      (node (ref "U3") (pin "14") (pinfunction "IO12_14") (pintype "bidirectional"))
    )
    (net (code "82") (name "unconnected-(U3-IO26-Pad11)") (class "Default")
      (node (ref "U3") (pin "11") (pinfunction "IO26_11") (pintype "bidirectional"))
    )
    (net (code "83") (name "unconnected-(U3-SCL{slash}CLK-Pad20)") (class "Default")
      (node (ref "U3") (pin "20") (pinfunction "SCL/CLK_20") (pintype "bidirectional"))
    )
    (net (code "84") (name "unconnected-(U3-SCS{slash}CMD-Pad19)") (class "Default")
      (node (ref "U3") (pin "19") (pinfunction "SCS/CMD_19") (pintype "bidirectional"))
    )
    (net (code "85") (name "unconnected-(U3-SDI{slash}SD1-Pad22)") (class "Default")
      (node (ref "U3") (pin "22") (pinfunction "SDI/SD1_22") (pintype "bidirectional"))
    )
    (net (code "86") (name "unconnected-(U3-SDO{slash}SD0-Pad21)") (class "Default")
      (node (ref "U3") (pin "21") (pinfunction "SDO/SD0_21") (pintype "bidirectional"))
    )
    (net (code "87") (name "unconnected-(U3-SHD{slash}SD2-Pad17)") (class "Default")
      (node (ref "U3") (pin "17") (pinfunction "SHD/SD2_17") (pintype "bidirectional"))
    )
    (net (code "88") (name "unconnected-(U3-SWP{slash}SD3-Pad18)") (class "Default")
      (node (ref "U3") (pin "18") (pinfunction "SWP/SD3_18") (pintype "bidirectional"))
    )
  )
)
